# LEDARRAY.net
KiCad netlist of a schematic drawn in EAGLE
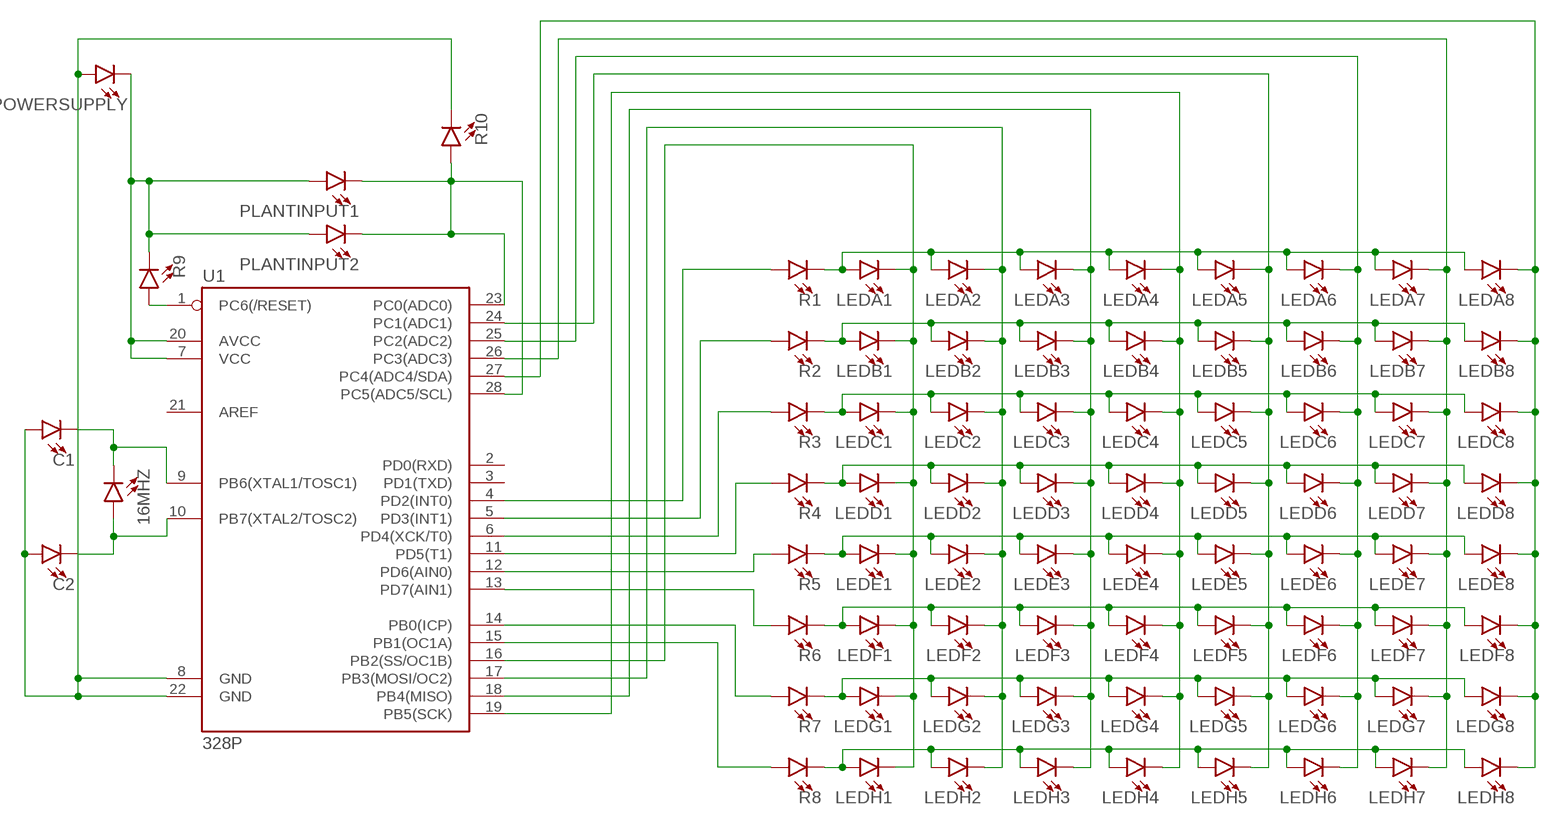
[diagram p0: schematic, sheet 1]

(export (version "E")
  (design (tool "Eeschema 10.0.6"))
  (components
    (comp (ref "16MHZ")
      (value "LED3MM")
      (footprint "eagle-import:LED_3MM")
      (libsource (lib "eagle-import") (part "LED3MM"))
    )
    (comp (ref "C1")
      (value "LED3MM")
      (footprint "eagle-import:LED_3MM")
      (libsource (lib "eagle-import") (part "LED3MM"))
    )
    (comp (ref "C2")
      (value "LED3MM")
      (footprint "eagle-import:LED_3MM")
      (libsource (lib "eagle-import") (part "LED3MM"))
    )
    (comp (ref "LEDA1")
      (value "LED3MM")
      (footprint "eagle-import:LED_3MM")
      (libsource (lib "eagle-import") (part "LED3MM"))
    )
    (comp (ref "LEDA2")
      (value "LED3MM")
      (footprint "eagle-import:LED_3MM")
      (libsource (lib "eagle-import") (part "LED3MM"))
    )
    (comp (ref "LEDA3")
      (value "LED3MM")
      (footprint "eagle-import:LED_3MM")
      (libsource (lib "eagle-import") (part "LED3MM"))
    )
    (comp (ref "LEDA4")
      (value "LED3MM")
      (footprint "eagle-import:LED_3MM")
      (libsource (lib "eagle-import") (part "LED3MM"))
    )
    (comp (ref "LEDA5")
      (value "LED3MM")
      (footprint "eagle-import:LED_3MM")
      (libsource (lib "eagle-import") (part "LED3MM"))
    )
    (comp (ref "LEDA6")
      (value "LED3MM")
      (footprint "eagle-import:LED_3MM")
      (libsource (lib "eagle-import") (part "LED3MM"))
    )
    (comp (ref "LEDA7")
      (value "LED3MM")
      (footprint "eagle-import:LED_3MM")
      (libsource (lib "eagle-import") (part "LED3MM"))
    )
    (comp (ref "LEDA8")
      (value "LED3MM")
      (footprint "eagle-import:LED_3MM")
      (libsource (lib "eagle-import") (part "LED3MM"))
    )
    (comp (ref "LEDB1")
      (value "LED3MM")
      (footprint "eagle-import:LED_3MM")
      (libsource (lib "eagle-import") (part "LED3MM"))
    )
    (comp (ref "LEDB2")
      (value "LED3MM")
      (footprint "eagle-import:LED_3MM")
      (libsource (lib "eagle-import") (part "LED3MM"))
    )
    (comp (ref "LEDB3")
      (value "LED3MM")
      (footprint "eagle-import:LED_3MM")
      (libsource (lib "eagle-import") (part "LED3MM"))
    )
    (comp (ref "LEDB4")
      (value "LED3MM")
      (footprint "eagle-import:LED_3MM")
      (libsource (lib "eagle-import") (part "LED3MM"))
    )
    (comp (ref "LEDB5")
      (value "LED3MM")
      (footprint "eagle-import:LED_3MM")
      (libsource (lib "eagle-import") (part "LED3MM"))
    )
    (comp (ref "LEDB6")
      (value "LED3MM")
      (footprint "eagle-import:LED_3MM")
      (libsource (lib "eagle-import") (part "LED3MM"))
    )
    (comp (ref "LEDB7")
      (value "LED3MM")
      (footprint "eagle-import:LED_3MM")
      (libsource (lib "eagle-import") (part "LED3MM"))
    )
    (comp (ref "LEDB8")
      (value "LED3MM")
      (footprint "eagle-import:LED_3MM")
      (libsource (lib "eagle-import") (part "LED3MM"))
    )
    (comp (ref "LEDC1")
      (value "LED3MM")
      (footprint "eagle-import:LED_3MM")
      (libsource (lib "eagle-import") (part "LED3MM"))
    )
    (comp (ref "LEDC2")
      (value "LED3MM")
      (footprint "eagle-import:LED_3MM")
      (libsource (lib "eagle-import") (part "LED3MM"))
    )
    (comp (ref "LEDC3")
      (value "LED3MM")
      (footprint "eagle-import:LED_3MM")
      (libsource (lib "eagle-import") (part "LED3MM"))
    )
    (comp (ref "LEDC4")
      (value "LED3MM")
      (footprint "eagle-import:LED_3MM")
      (libsource (lib "eagle-import") (part "LED3MM"))
    )
    (comp (ref "LEDC5")
      (value "LED3MM")
      (footprint "eagle-import:LED_3MM")
      (libsource (lib "eagle-import") (part "LED3MM"))
    )
    (comp (ref "LEDC6")
      (value "LED3MM")
      (footprint "eagle-import:LED_3MM")
      (libsource (lib "eagle-import") (part "LED3MM"))
    )
    (comp (ref "LEDC7")
      (value "LED3MM")
      (footprint "eagle-import:LED_3MM")
      (libsource (lib "eagle-import") (part "LED3MM"))
    )
    (comp (ref "LEDC8")
      (value "LED3MM")
      (footprint "eagle-import:LED_3MM")
      (libsource (lib "eagle-import") (part "LED3MM"))
    )
    (comp (ref "LEDD1")
      (value "LED3MM")
      (footprint "eagle-import:LED_3MM")
      (libsource (lib "eagle-import") (part "LED3MM"))
    )
    (comp (ref "LEDD2")
      (value "LED3MM")
      (footprint "eagle-import:LED_3MM")
      (libsource (lib "eagle-import") (part "LED3MM"))
    )
    (comp (ref "LEDD3")
      (value "LED3MM")
      (footprint "eagle-import:LED_3MM")
      (libsource (lib "eagle-import") (part "LED3MM"))
    )
    (comp (ref "LEDD4")
      (value "LED3MM")
      (footprint "eagle-import:LED_3MM")
      (libsource (lib "eagle-import") (part "LED3MM"))
    )
    (comp (ref "LEDD5")
      (value "LED3MM")
      (footprint "eagle-import:LED_3MM")
      (libsource (lib "eagle-import") (part "LED3MM"))
    )
    (comp (ref "LEDD6")
      (value "LED3MM")
      (footprint "eagle-import:LED_3MM")
      (libsource (lib "eagle-import") (part "LED3MM"))
    )
    (comp (ref "LEDD7")
      (value "LED3MM")
      (footprint "eagle-import:LED_3MM")
      (libsource (lib "eagle-import") (part "LED3MM"))
    )
    (comp (ref "LEDD8")
      (value "LED3MM")
      (footprint "eagle-import:LED_3MM")
      (libsource (lib "eagle-import") (part "LED3MM"))
    )
    (comp (ref "LEDE1")
      (value "LED3MM")
      (footprint "eagle-import:LED_3MM")
      (libsource (lib "eagle-import") (part "LED3MM"))
    )
    (comp (ref "LEDE2")
      (value "LED3MM")
      (footprint "eagle-import:LED_3MM")
      (libsource (lib "eagle-import") (part "LED3MM"))
    )
    (comp (ref "LEDE3")
      (value "LED3MM")
      (footprint "eagle-import:LED_3MM")
      (libsource (lib "eagle-import") (part "LED3MM"))
    )
    (comp (ref "LEDE4")
      (value "LED3MM")
      (footprint "eagle-import:LED_3MM")
      (libsource (lib "eagle-import") (part "LED3MM"))
    )
    (comp (ref "LEDE5")
      (value "LED3MM")
      (footprint "eagle-import:LED_3MM")
      (libsource (lib "eagle-import") (part "LED3MM"))
    )
    (comp (ref "LEDE6")
      (value "LED3MM")
      (footprint "eagle-import:LED_3MM")
      (libsource (lib "eagle-import") (part "LED3MM"))
    )
    (comp (ref "LEDE7")
      (value "LED3MM")
      (footprint "eagle-import:LED_3MM")
      (libsource (lib "eagle-import") (part "LED3MM"))
    )
    (comp (ref "LEDE8")
      (value "LED3MM")
      (footprint "eagle-import:LED_3MM")
      (libsource (lib "eagle-import") (part "LED3MM"))
    )
    (comp (ref "LEDF1")
      (value "LED3MM")
      (footprint "eagle-import:LED_3MM")
      (libsource (lib "eagle-import") (part "LED3MM"))
    )
    (comp (ref "LEDF2")
      (value "LED3MM")
      (footprint "eagle-import:LED_3MM")
      (libsource (lib "eagle-import") (part "LED3MM"))
    )
    (comp (ref "LEDF3")
      (value "LED3MM")
      (footprint "eagle-import:LED_3MM")
      (libsource (lib "eagle-import") (part "LED3MM"))
    )
    (comp (ref "LEDF4")
      (value "LED3MM")
      (footprint "eagle-import:LED_3MM")
      (libsource (lib "eagle-import") (part "LED3MM"))
    )
    (comp (ref "LEDF5")
      (value "LED3MM")
      (footprint "eagle-import:LED_3MM")
      (libsource (lib "eagle-import") (part "LED3MM"))
    )
    (comp (ref "LEDF6")
      (value "LED3MM")
      (footprint "eagle-import:LED_3MM")
      (libsource (lib "eagle-import") (part "LED3MM"))
    )
    (comp (ref "LEDF7")
      (value "LED3MM")
      (footprint "eagle-import:LED_3MM")
      (libsource (lib "eagle-import") (part "LED3MM"))
    )
    (comp (ref "LEDF8")
      (value "LED3MM")
      (footprint "eagle-import:LED_3MM")
      (libsource (lib "eagle-import") (part "LED3MM"))
    )
    (comp (ref "LEDG1")
      (value "LED3MM")
      (footprint "eagle-import:LED_3MM")
      (libsource (lib "eagle-import") (part "LED3MM"))
    )
    (comp (ref "LEDG2")
      (value "LED3MM")
      (footprint "eagle-import:LED_3MM")
      (libsource (lib "eagle-import") (part "LED3MM"))
    )
    (comp (ref "LEDG3")
      (value "LED3MM")
      (footprint "eagle-import:LED_3MM")
      (libsource (lib "eagle-import") (part "LED3MM"))
    )
    (comp (ref "LEDG4")
      (value "LED3MM")
      (footprint "eagle-import:LED_3MM")
      (libsource (lib "eagle-import") (part "LED3MM"))
    )
    (comp (ref "LEDG5")
      (value "LED3MM")
      (footprint "eagle-import:LED_3MM")
      (libsource (lib "eagle-import") (part "LED3MM"))
    )
    (comp (ref "LEDG6")
      (value "LED3MM")
      (footprint "eagle-import:LED_3MM")
      (libsource (lib "eagle-import") (part "LED3MM"))
    )
    (comp (ref "LEDG7")
      (value "LED3MM")
      (footprint "eagle-import:LED_3MM")
      (libsource (lib "eagle-import") (part "LED3MM"))
    )
    (comp (ref "LEDG8")
      (value "LED3MM")
      (footprint "eagle-import:LED_3MM")
      (libsource (lib "eagle-import") (part "LED3MM"))
    )
    (comp (ref "LEDH1")
      (value "LED3MM")
      (footprint "eagle-import:LED_3MM")
      (libsource (lib "eagle-import") (part "LED3MM"))
    )
    (comp (ref "LEDH2")
      (value "LED3MM")
      (footprint "eagle-import:LED_3MM")
      (libsource (lib "eagle-import") (part "LED3MM"))
    )
    (comp (ref "LEDH3")
      (value "LED3MM")
      (footprint "eagle-import:LED_3MM")
      (libsource (lib "eagle-import") (part "LED3MM"))
    )
    (comp (ref "LEDH4")
      (value "LED3MM")
      (footprint "eagle-import:LED_3MM")
      (libsource (lib "eagle-import") (part "LED3MM"))
    )
    (comp (ref "LEDH5")
      (value "LED3MM")
      (footprint "eagle-import:LED_3MM")
      (libsource (lib "eagle-import") (part "LED3MM"))
    )
    (comp (ref "LEDH6")
      (value "LED3MM")
      (footprint "eagle-import:LED_3MM")
      (libsource (lib "eagle-import") (part "LED3MM"))
    )
    (comp (ref "LEDH7")
      (value "LED3MM")
      (footprint "eagle-import:LED_3MM")
      (libsource (lib "eagle-import") (part "LED3MM"))
    )
    (comp (ref "LEDH8")
      (value "LED3MM")
      (footprint "eagle-import:LED_3MM")
      (libsource (lib "eagle-import") (part "LED3MM"))
    )
    (comp (ref "PLANTINPUT1")
      (value "LED3MM")
      (footprint "eagle-import:LED_3MM")
      (libsource (lib "eagle-import") (part "LED3MM"))
    )
    (comp (ref "PLANTINPUT2")
      (value "LED3MM")
      (footprint "eagle-import:LED_3MM")
      (libsource (lib "eagle-import") (part "LED3MM"))
    )
    (comp (ref "POWERSUPPLY")
      (value "LED3MM")
      (footprint "eagle-import:LED_3MM")
      (libsource (lib "eagle-import") (part "LED3MM"))
    )
    (comp (ref "R1")
      (value "LED3MM")
      (footprint "eagle-import:LED_3MM")
      (libsource (lib "eagle-import") (part "LED3MM"))
    )
    (comp (ref "R2")
      (value "LED3MM")
      (footprint "eagle-import:LED_3MM")
      (libsource (lib "eagle-import") (part "LED3MM"))
    )
    (comp (ref "R3")
      (value "LED3MM")
      (footprint "eagle-import:LED_3MM")
      (libsource (lib "eagle-import") (part "LED3MM"))
    )
    (comp (ref "R4")
      (value "LED3MM")
      (footprint "eagle-import:LED_3MM")
      (libsource (lib "eagle-import") (part "LED3MM"))
    )
    (comp (ref "R5")
      (value "LED3MM")
      (footprint "eagle-import:LED_3MM")
      (libsource (lib "eagle-import") (part "LED3MM"))
    )
    (comp (ref "R6")
      (value "LED3MM")
      (footprint "eagle-import:LED_3MM")
      (libsource (lib "eagle-import") (part "LED3MM"))
    )
    (comp (ref "R7")
      (value "LED3MM")
      (footprint "eagle-import:LED_3MM")
      (libsource (lib "eagle-import") (part "LED3MM"))
    )
    (comp (ref "R8")
      (value "LED3MM")
      (footprint "eagle-import:LED_3MM")
      (libsource (lib "eagle-import") (part "LED3MM"))
    )
    (comp (ref "R9")
      (value "LED3MM")
      (footprint "eagle-import:LED_3MM")
      (libsource (lib "eagle-import") (part "LED3MM"))
    )
    (comp (ref "R10")
      (value "LED3MM")
      (footprint "eagle-import:LED_3MM")
      (libsource (lib "eagle-import") (part "LED3MM"))
    )
    (comp (ref "U1")
      (value "328P")
      (footprint "eagle-import:DIP28")
      (libsource (lib "eagle-import") (part "ATMEGA328P_PDIP"))
    )
  )
  (nets
    (net (code "1") (name "Net-(16MHZ-C)") (class "Default")
      (node (ref "16MHZ") (pin "K") (pinfunction "C_K") (pintype "passive"))
      (node (ref "C1") (pin "K") (pinfunction "C_K") (pintype "passive"))
      (node (ref "U1") (pin "9") (pinfunction "PB6(XTAL1/TOSC1)_9") (pintype "bidirectional"))
    )
    (net (code "2") (name "Net-(C2-C)") (class "Default")
      (node (ref "16MHZ") (pin "A") (pinfunction "A_A") (pintype "passive"))
      (node (ref "C2") (pin "K") (pinfunction "C_K") (pintype "passive"))
      (node (ref "U1") (pin "10") (pinfunction "PB7(XTAL2/TOSC2)_10") (pintype "bidirectional"))
    )
    (net (code "3") (name "Net-(LEDA1-C)") (class "Default")
      (node (ref "LEDA1") (pin "K") (pinfunction "C_K") (pintype "passive"))
      (node (ref "LEDB1") (pin "K") (pinfunction "C_K") (pintype "passive"))
      (node (ref "LEDC1") (pin "K") (pinfunction "C_K") (pintype "passive"))
      (node (ref "LEDD1") (pin "K") (pinfunction "C_K") (pintype "passive"))
      (node (ref "LEDE1") (pin "K") (pinfunction "C_K") (pintype "passive"))
      (node (ref "LEDF1") (pin "K") (pinfunction "C_K") (pintype "passive"))
      (node (ref "LEDG1") (pin "K") (pinfunction "C_K") (pintype "passive"))
      (node (ref "LEDH1") (pin "K") (pinfunction "C_K") (pintype "passive"))
      (node (ref "U1") (pin "16") (pinfunction "PB2(SS/OC1B)_16") (pintype "bidirectional"))
    )
    (net (code "4") (name "Net-(LEDA2-C)") (class "Default")
      (node (ref "LEDA2") (pin "K") (pinfunction "C_K") (pintype "passive"))
      (node (ref "LEDB2") (pin "K") (pinfunction "C_K") (pintype "passive"))
      (node (ref "LEDC2") (pin "K") (pinfunction "C_K") (pintype "passive"))
      (node (ref "LEDD2") (pin "K") (pinfunction "C_K") (pintype "passive"))
      (node (ref "LEDE2") (pin "K") (pinfunction "C_K") (pintype "passive"))
      (node (ref "LEDF2") (pin "K") (pinfunction "C_K") (pintype "passive"))
      (node (ref "LEDG2") (pin "K") (pinfunction "C_K") (pintype "passive"))
      (node (ref "LEDH2") (pin "K") (pinfunction "C_K") (pintype "passive"))
      (node (ref "U1") (pin "17") (pinfunction "PB3(MOSI/OC2)_17") (pintype "bidirectional"))
    )
    (net (code "5") (name "Net-(LEDA3-C)") (class "Default")
      (node (ref "LEDA3") (pin "K") (pinfunction "C_K") (pintype "passive"))
      (node (ref "LEDB3") (pin "K") (pinfunction "C_K") (pintype "passive"))
      (node (ref "LEDC3") (pin "K") (pinfunction "C_K") (pintype "passive"))
      (node (ref "LEDD3") (pin "K") (pinfunction "C_K") (pintype "passive"))
      (node (ref "LEDE3") (pin "K") (pinfunction "C_K") (pintype "passive"))
      (node (ref "LEDF3") (pin "K") (pinfunction "C_K") (pintype "passive"))
      (node (ref "LEDG3") (pin "K") (pinfunction "C_K") (pintype "passive"))
      (node (ref "LEDH3") (pin "K") (pinfunction "C_K") (pintype "passive"))
      (node (ref "U1") (pin "18") (pinfunction "PB4(MISO)_18") (pintype "bidirectional"))
    )
    (net (code "6") (name "Net-(LEDA4-C)") (class "Default")
      (node (ref "LEDA4") (pin "K") (pinfunction "C_K") (pintype "passive"))
      (node (ref "LEDB4") (pin "K") (pinfunction "C_K") (pintype "passive"))
      (node (ref "LEDC4") (pin "K") (pinfunction "C_K") (pintype "passive"))
      (node (ref "LEDD4") (pin "K") (pinfunction "C_K") (pintype "passive"))
      (node (ref "LEDE4") (pin "K") (pinfunction "C_K") (pintype "passive"))
      (node (ref "LEDF4") (pin "K") (pinfunction "C_K") (pintype "passive"))
      (node (ref "LEDG4") (pin "K") (pinfunction "C_K") (pintype "passive"))
      (node (ref "LEDH4") (pin "K") (pinfunction "C_K") (pintype "passive"))
      (node (ref "U1") (pin "19") (pinfunction "PB5(SCK)_19") (pintype "bidirectional"))
    )
    (net (code "7") (name "Net-(LEDA5-C)") (class "Default")
      (node (ref "LEDA5") (pin "K") (pinfunction "C_K") (pintype "passive"))
      (node (ref "LEDB5") (pin "K") (pinfunction "C_K") (pintype "passive"))
      (node (ref "LEDC5") (pin "K") (pinfunction "C_K") (pintype "passive"))
      (node (ref "LEDD5") (pin "K") (pinfunction "C_K") (pintype "passive"))
      (node (ref "LEDE5") (pin "K") (pinfunction "C_K") (pintype "passive"))
      (node (ref "LEDF5") (pin "K") (pinfunction "C_K") (pintype "passive"))
      (node (ref "LEDG5") (pin "K") (pinfunction "C_K") (pintype "passive"))
      (node (ref "LEDH5") (pin "K") (pinfunction "C_K") (pintype "passive"))
      (node (ref "U1") (pin "24") (pinfunction "PC1(ADC1)_24") (pintype "bidirectional"))
    )
    (net (code "8") (name "Net-(LEDA6-C)") (class "Default")
      (node (ref "LEDA6") (pin "K") (pinfunction "C_K") (pintype "passive"))
      (node (ref "LEDB6") (pin "K") (pinfunction "C_K") (pintype "passive"))
      (node (ref "LEDC6") (pin "K") (pinfunction "C_K") (pintype "passive"))
      (node (ref "LEDD6") (pin "K") (pinfunction "C_K") (pintype "passive"))
      (node (ref "LEDE6") (pin "K") (pinfunction "C_K") (pintype "passive"))
      (node (ref "LEDF6") (pin "K") (pinfunction "C_K") (pintype "passive"))
      (node (ref "LEDG6") (pin "K") (pinfunction "C_K") (pintype "passive"))
      (node (ref "LEDH6") (pin "K") (pinfunction "C_K") (pintype "passive"))
      (node (ref "U1") (pin "25") (pinfunction "PC2(ADC2)_25") (pintype "bidirectional"))
    )
    (net (code "9") (name "Net-(LEDA7-C)") (class "Default")
      (node (ref "LEDA7") (pin "K") (pinfunction "C_K") (pintype "passive"))
      (node (ref "LEDB7") (pin "K") (pinfunction "C_K") (pintype "passive"))
      (node (ref "LEDC7") (pin "K") (pinfunction "C_K") (pintype "passive"))
      (node (ref "LEDD7") (pin "K") (pinfunction "C_K") (pintype "passive"))
      (node (ref "LEDE7") (pin "K") (pinfunction "C_K") (pintype "passive"))
      (node (ref "LEDF7") (pin "K") (pinfunction "C_K") (pintype "passive"))
      (node (ref "LEDG7") (pin "K") (pinfunction "C_K") (pintype "passive"))
      (node (ref "LEDH7") (pin "K") (pinfunction "C_K") (pintype "passive"))
      (node (ref "U1") (pin "26") (pinfunction "PC3(ADC3)_26") (pintype "bidirectional"))
    )
    (net (code "10") (name "Net-(LEDA8-C)") (class "Default")
      (node (ref "LEDA8") (pin "K") (pinfunction "C_K") (pintype "passive"))
      (node (ref "LEDB8") (pin "K") (pinfunction "C_K") (pintype "passive"))
      (node (ref "LEDC8") (pin "K") (pinfunction "C_K") (pintype "passive"))
      (node (ref "LEDD8") (pin "K") (pinfunction "C_K") (pintype "passive"))
      (node (ref "LEDE8") (pin "K") (pinfunction "C_K") (pintype "passive"))
      (node (ref "LEDF8") (pin "K") (pinfunction "C_K") (pintype "passive"))
      (node (ref "LEDG8") (pin "K") (pinfunction "C_K") (pintype "passive"))
      (node (ref "LEDH8") (pin "K") (pinfunction "C_K") (pintype "passive"))
      (node (ref "U1") (pin "27") (pinfunction "PC4(ADC4/SDA)_27") (pintype "bidirectional"))
    )
    (net (code "11") (name "Net-(PLANTINPUT1-C)") (class "Default")
      (node (ref "PLANTINPUT1") (pin "K") (pinfunction "C_K") (pintype "passive"))
      (node (ref "PLANTINPUT2") (pin "K") (pinfunction "C_K") (pintype "passive"))
      (node (ref "R10") (pin "A") (pinfunction "A_A") (pintype "passive"))
      (node (ref "U1") (pin "23") (pinfunction "PC0(ADC0)_23") (pintype "bidirectional"))
      (node (ref "U1") (pin "28") (pinfunction "PC5(ADC5/SCL)_28") (pintype "bidirectional"))
    )
    (net (code "12") (name "Net-(POWERSUPPLY-C)") (class "Default")
      (node (ref "PLANTINPUT1") (pin "A") (pinfunction "A_A") (pintype "passive"))
      (node (ref "PLANTINPUT2") (pin "A") (pinfunction "A_A") (pintype "passive"))
      (node (ref "POWERSUPPLY") (pin "K") (pinfunction "C_K") (pintype "passive"))
      (node (ref "R9") (pin "K") (pinfunction "C_K") (pintype "passive"))
      (node (ref "U1") (pin "20") (pinfunction "AVCC_20") (pintype "bidirectional"))
      (node (ref "U1") (pin "7") (pinfunction "VCC_7") (pintype "bidirectional"))
    )
    (net (code "13") (name "Net-(R1-C)") (class "Default")
      (node (ref "LEDA1") (pin "A") (pinfunction "A_A") (pintype "passive"))
      (node (ref "LEDA2") (pin "A") (pinfunction "A_A") (pintype "passive"))
      (node (ref "LEDA3") (pin "A") (pinfunction "A_A") (pintype "passive"))
      (node (ref "LEDA4") (pin "A") (pinfunction "A_A") (pintype "passive"))
      (node (ref "LEDA5") (pin "A") (pinfunction "A_A") (pintype "passive"))
      (node (ref "LEDA6") (pin "A") (pinfunction "A_A") (pintype "passive"))
      (node (ref "LEDA7") (pin "A") (pinfunction "A_A") (pintype "passive"))
      (node (ref "LEDA8") (pin "A") (pinfunction "A_A") (pintype "passive"))
      (node (ref "R1") (pin "K") (pinfunction "C_K") (pintype "passive"))
    )
    (net (code "14") (name "Net-(R2-C)") (class "Default")
      (node (ref "LEDB1") (pin "A") (pinfunction "A_A") (pintype "passive"))
      (node (ref "LEDB2") (pin "A") (pinfunction "A_A") (pintype "passive"))
      (node (ref "LEDB3") (pin "A") (pinfunction "A_A") (pintype "passive"))
      (node (ref "LEDB4") (pin "A") (pinfunction "A_A") (pintype "passive"))
      (node (ref "LEDB5") (pin "A") (pinfunction "A_A") (pintype "passive"))
      (node (ref "LEDB6") (pin "A") (pinfunction "A_A") (pintype "passive"))
      (node (ref "LEDB7") (pin "A") (pinfunction "A_A") (pintype "passive"))
      (node (ref "LEDB8") (pin "A") (pinfunction "A_A") (pintype "passive"))
      (node (ref "R2") (pin "K") (pinfunction "C_K") (pintype "passive"))
    )
    (net (code "15") (name "Net-(R3-C)") (class "Default")
      (node (ref "LEDC1") (pin "A") (pinfunction "A_A") (pintype "passive"))
      (node (ref "LEDC2") (pin "A") (pinfunction "A_A") (pintype "passive"))
      (node (ref "LEDC3") (pin "A") (pinfunction "A_A") (pintype "passive"))
      (node (ref "LEDC4") (pin "A") (pinfunction "A_A") (pintype "passive"))
      (node (ref "LEDC5") (pin "A") (pinfunction "A_A") (pintype "passive"))
      (node (ref "LEDC6") (pin "A") (pinfunction "A_A") (pintype "passive"))
      (node (ref "LEDC7") (pin "A") (pinfunction "A_A") (pintype "passive"))
      (node (ref "LEDC8") (pin "A") (pinfunction "A_A") (pintype "passive"))
      (node (ref "R3") (pin "K") (pinfunction "C_K") (pintype "passive"))
    )
    (net (code "16") (name "Net-(R4-C)") (class "Default")
      (node (ref "LEDD1") (pin "A") (pinfunction "A_A") (pintype "passive"))
      (node (ref "LEDD2") (pin "A") (pinfunction "A_A") (pintype "passive"))
      (node (ref "LEDD3") (pin "A") (pinfunction "A_A") (pintype "passive"))
      (node (ref "LEDD4") (pin "A") (pinfunction "A_A") (pintype "passive"))
      (node (ref "LEDD5") (pin "A") (pinfunction "A_A") (pintype "passive"))
      (node (ref "LEDD6") (pin "A") (pinfunction "A_A") (pintype "passive"))
      (node (ref "LEDD7") (pin "A") (pinfunction "A_A") (pintype "passive"))
      (node (ref "LEDD8") (pin "A") (pinfunction "A_A") (pintype "passive"))
      (node (ref "R4") (pin "K") (pinfunction "C_K") (pintype "passive"))
    )
    (net (code "17") (name "Net-(R5-C)") (class "Default")
      (node (ref "LEDE1") (pin "A") (pinfunction "A_A") (pintype "passive"))
      (node (ref "LEDE2") (pin "A") (pinfunction "A_A") (pintype "passive"))
      (node (ref "LEDE3") (pin "A") (pinfunction "A_A") (pintype "passive"))
      (node (ref "LEDE4") (pin "A") (pinfunction "A_A") (pintype "passive"))
      (node (ref "LEDE5") (pin "A") (pinfunction "A_A") (pintype "passive"))
      (node (ref "LEDE6") (pin "A") (pinfunction "A_A") (pintype "passive"))
      (node (ref "LEDE7") (pin "A") (pinfunction "A_A") (pintype "passive"))
      (node (ref "LEDE8") (pin "A") (pinfunction "A_A") (pintype "passive"))
      (node (ref "R5") (pin "K") (pinfunction "C_K") (pintype "passive"))
    )
    (net (code "18") (name "Net-(R6-C)") (class "Default")
      (node (ref "LEDF1") (pin "A") (pinfunction "A_A") (pintype "passive"))
      (node (ref "LEDF2") (pin "A") (pinfunction "A_A") (pintype "passive"))
      (node (ref "LEDF3") (pin "A") (pinfunction "A_A") (pintype "passive"))
      (node (ref "LEDF4") (pin "A") (pinfunction "A_A") (pintype "passive"))
      (node (ref "LEDF5") (pin "A") (pinfunction "A_A") (pintype "passive"))
      (node (ref "LEDF6") (pin "A") (pinfunction "A_A") (pintype "passive"))
      (node (ref "LEDF7") (pin "A") (pinfunction "A_A") (pintype "passive"))
      (node (ref "LEDF8") (pin "A") (pinfunction "A_A") (pintype "passive"))
      (node (ref "R6") (pin "K") (pinfunction "C_K") (pintype "passive"))
    )
    (net (code "19") (name "Net-(R7-C)") (class "Default")
      (node (ref "LEDG1") (pin "A") (pinfunction "A_A") (pintype "passive"))
      (node (ref "LEDG2") (pin "A") (pinfunction "A_A") (pintype "passive"))
      (node (ref "LEDG3") (pin "A") (pinfunction "A_A") (pintype "passive"))
      (node (ref "LEDG4") (pin "A") (pinfunction "A_A") (pintype "passive"))
      (node (ref "LEDG5") (pin "A") (pinfunction "A_A") (pintype "passive"))
      (node (ref "LEDG6") (pin "A") (pinfunction "A_A") (pintype "passive"))
      (node (ref "LEDG7") (pin "A") (pinfunction "A_A") (pintype "passive"))
      (node (ref "LEDG8") (pin "A") (pinfunction "A_A") (pintype "passive"))
      (node (ref "R7") (pin "K") (pinfunction "C_K") (pintype "passive"))
    )
    (net (code "20") (name "Net-(R8-C)") (class "Default")
      (node (ref "LEDH1") (pin "A") (pinfunction "A_A") (pintype "passive"))
      (node (ref "LEDH2") (pin "A") (pinfunction "A_A") (pintype "passive"))
      (node (ref "LEDH3") (pin "A") (pinfunction "A_A") (pintype "passive"))
      (node (ref "LEDH4") (pin "A") (pinfunction "A_A") (pintype "passive"))
      (node (ref "LEDH5") (pin "A") (pinfunction "A_A") (pintype "passive"))
      (node (ref "LEDH6") (pin "A") (pinfunction "A_A") (pintype "passive"))
      (node (ref "LEDH7") (pin "A") (pinfunction "A_A") (pintype "passive"))
      (node (ref "LEDH8") (pin "A") (pinfunction "A_A") (pintype "passive"))
      (node (ref "R8") (pin "K") (pinfunction "C_K") (pintype "passive"))
    )
    (net (code "21") (name "Net-(R10-C)") (class "Default")
      (node (ref "C1") (pin "A") (pinfunction "A_A") (pintype "passive"))
      (node (ref "C2") (pin "A") (pinfunction "A_A") (pintype "passive"))
      (node (ref "POWERSUPPLY") (pin "A") (pinfunction "A_A") (pintype "passive"))
      (node (ref "R10") (pin "K") (pinfunction "C_K") (pintype "passive"))
      (node (ref "U1") (pin "22") (pinfunction "GND_22") (pintype "bidirectional"))
      (node (ref "U1") (pin "8") (pinfunction "GND_8") (pintype "bidirectional"))
    )
    (net (code "22") (name "Net-(U1-PB0(ICP))") (class "Default")
      (node (ref "R7") (pin "A") (pinfunction "A_A") (pintype "passive"))
      (node (ref "U1") (pin "14") (pinfunction "PB0(ICP)_14") (pintype "bidirectional"))
    )
    (net (code "23") (name "Net-(U1-PB1(OC1A))") (class "Default")
      (node (ref "R8") (pin "A") (pinfunction "A_A") (pintype "passive"))
      (node (ref "U1") (pin "15") (pinfunction "PB1(OC1A)_15") (pintype "bidirectional"))
    )
    (net (code "24") (name "Net-(U1-PC6({slash}RESET))") (class "Default")
      (node (ref "R9") (pin "A") (pinfunction "A_A") (pintype "passive"))
      (node (ref "U1") (pin "1") (pinfunction "PC6(/RESET)_1") (pintype "bidirectional"))
    )
    (net (code "25") (name "Net-(U1-PD2(INT0))") (class "Default")
      (node (ref "R1") (pin "A") (pinfunction "A_A") (pintype "passive"))
      (node (ref "U1") (pin "4") (pinfunction "PD2(INT0)_4") (pintype "bidirectional"))
    )
    (net (code "26") (name "Net-(U1-PD3(INT1))") (class "Default")
      (node (ref "R2") (pin "A") (pinfunction "A_A") (pintype "passive"))
      (node (ref "U1") (pin "5") (pinfunction "PD3(INT1)_5") (pintype "bidirectional"))
    )
    (net (code "27") (name "Net-(U1-PD4(XCK{slash}T0))") (class "Default")
      (node (ref "R3") (pin "A") (pinfunction "A_A") (pintype "passive"))
      (node (ref "U1") (pin "6") (pinfunction "PD4(XCK/T0)_6") (pintype "bidirectional"))
    )
    (net (code "28") (name "Net-(U1-PD5(T1))") (class "Default")
      (node (ref "R4") (pin "A") (pinfunction "A_A") (pintype "passive"))
      (node (ref "U1") (pin "11") (pinfunction "PD5(T1)_11") (pintype "bidirectional"))
    )
    (net (code "29") (name "Net-(U1-PD6(AIN0))") (class "Default")
      (node (ref "R5") (pin "A") (pinfunction "A_A") (pintype "passive"))
      (node (ref "U1") (pin "12") (pinfunction "PD6(AIN0)_12") (pintype "bidirectional"))
    )
    (net (code "30") (name "Net-(U1-PD7(AIN1))") (class "Default")
      (node (ref "R6") (pin "A") (pinfunction "A_A") (pintype "passive"))
      (node (ref "U1") (pin "13") (pinfunction "PD7(AIN1)_13") (pintype "bidirectional"))
    )
    (net (code "31") (name "unconnected-(U1-AREF-Pad21)") (class "Default")
      (node (ref "U1") (pin "21") (pinfunction "AREF_21") (pintype "bidirectional"))
    )
    (net (code "32") (name "unconnected-(U1-PD0(RXD)-Pad2)") (class "Default")
      (node (ref "U1") (pin "2") (pinfunction "PD0(RXD)_2") (pintype "bidirectional"))
    )
    (net (code "33") (name "unconnected-(U1-PD1(TXD)-Pad3)") (class "Default")
      (node (ref "U1") (pin "3") (pinfunction "PD1(TXD)_3") (pintype "bidirectional"))
    )
  )
)
